# LMR514203_3V.net
KiCad netlist of a schematic drawn in Altium Designer
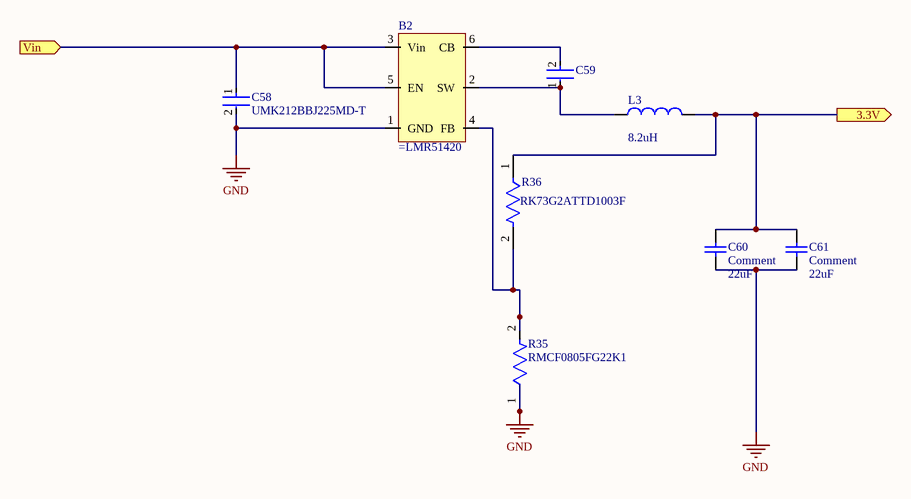
[diagram p0: LMR514203.3V.SchDoc]

(export (version "E")
  (design (tool "Eeschema 10.0.6"))
  (components
    (comp (ref "B2")
      (value "~")
      (footprint "LMR51420:PCBComponent_1")
      (libsource (lib "LMR51420") (part "Component_1"))
    )
    (comp (ref "C58")
      (value "UMK212BBJ225MD-T")
      (footprint "FP-0805-L_2_0_0_2-W_1_25-IPC_A")
      (description "Multilayer Ceramic Capacitor 2.2uF 50V X5R 20% SMD 0803 T/R")
      (fields (field (name "TOLERANCE") "20%"))
      (libsource (lib "Altium Content Vault") (part "02cd4be3c70576c341d710602a673aa"))
    )
    (comp (ref "C59")
      (value "C0603C104K4PAC7867")
      (footprint "FP-C0603C-CF-MFG")
      (description "CAP CER 0.1UF 16V X5R 0603")
      (fields
        (field (name "OCTOPART") "https://octopart.com/c0603c104k4pactu-kemet-12592163")
        (field (name "MANUFACTURER") "KEMET")
      )
      (libsource (lib "Altium Content Vault") (part "b4654b650e69147ec39a6b967a45e02"))
    )
    (comp (ref "C60")
      (value "Comment")
      (footprint "Cap22uF_C1206C226M4PAC7800")
      (description "Capacitor")
      (fields (field (name "ALTIUM_VALUE") "22uF") (field (name "PUBLISHER") "Altium Limited"))
      (libsource (lib "Miscellaneous Devices") (part "Cap"))
    )
    (comp (ref "C61")
      (value "Comment")
      (footprint "Cap22uF_C1206C226M4PAC7800")
      (description "Capacitor")
      (fields (field (name "ALTIUM_VALUE") "22uF") (field (name "PUBLISHER") "Altium Limited"))
      (libsource (lib "Miscellaneous Devices") (part "Cap"))
    )
    (comp (ref "L3")
      (value "8.2uH")
      (footprint "0402-A")
      (description "Inductor")
      (fields (field (name "Comment") "MSS1260H-822MED") (field (name "PUBLISHER") "Altium Limited"))
      (libsource (lib "Miscellaneous Devices") (part "Inductor"))
    )
    (comp (ref "R35")
      (value "RMCF0805FG22K1")
      (footprint "FP-RMCF0805-IPC_B")
      (description "22.1kΩ ±1% 0.125W 0805 Thick Film Chip Resistor AEC-Q200 compliant")
      (fields (field (name "TOLERANCE") "1%"))
      (libsource (lib "Altium Content Vault") (part "1029c3af85768c4190bb7ad29bc67b5"))
    )
    (comp (ref "R36")
      (value "RK73G2ATTD1003F")
      (footprint "FP-RK73G2A-IPC_A")
      (description "100kΩ ±1% 0.125W Chip Resistor 0805 Thick Film AEC-Q200 Qualified")
      (fields (field (name "TOLERANCE") "1%"))
      (libsource (lib "Altium Content Vault") (part "1029c3af85768c4190bb7ad29bc67b5"))
    )
  )
  (nets
    (net (code "1") (name "/3.3V") (class "Default")
      (node (ref "C60") (pin "2") (pinfunction "2_2") (pintype "passive"))
      (node (ref "C61") (pin "2") (pinfunction "2_2") (pintype "passive"))
      (node (ref "L3") (pin "2") (pinfunction "2_2") (pintype "passive"))
      (node (ref "R36") (pin "1") (pinfunction "1_1") (pintype "passive"))
    )
    (net (code "2") (name "/Vin") (class "Default")
      (node (ref "B2") (pin "3") (pinfunction "Vin_3") (pintype "passive"))
      (node (ref "B2") (pin "5") (pinfunction "EN_5") (pintype "passive"))
      (node (ref "C58") (pin "1") (pinfunction "1_1") (pintype "passive"))
    )
    (net (code "3") (name "GND") (class "Default")
      (node (ref "B2") (pin "1") (pinfunction "GND_1") (pintype "passive"))
      (node (ref "C58") (pin "2") (pinfunction "2_2") (pintype "passive"))
      (node (ref "C60") (pin "1") (pinfunction "1_1") (pintype "passive"))
      (node (ref "C61") (pin "1") (pinfunction "1_1") (pintype "passive"))
      (node (ref "R35") (pin "1") (pinfunction "1_1") (pintype "passive"))
    )
    (net (code "4") (name "Net-(B2-CB)") (class "Default")
      (node (ref "B2") (pin "6") (pinfunction "CB_6") (pintype "passive"))
      (node (ref "C59") (pin "2") (pinfunction "2_2") (pintype "passive"))
    )
    (net (code "5") (name "Net-(B2-FB)") (class "Default")
      (node (ref "B2") (pin "4") (pinfunction "FB_4") (pintype "passive"))
      (node (ref "R35") (pin "2") (pinfunction "2_2") (pintype "passive"))
      (node (ref "R36") (pin "2") (pinfunction "2_2") (pintype "passive"))
    )
    (net (code "6") (name "Net-(B2-SW)") (class "Default")
      (node (ref "B2") (pin "2") (pinfunction "SW_2") (pintype "passive"))
      (node (ref "C59") (pin "1") (pinfunction "1_1") (pintype "passive"))
      (node (ref "L3") (pin "1") (pinfunction "1_1") (pintype "passive"))
    )
  )
)
